# Sheet_1_2021-03-18.net
KiCad netlist of a schematic drawn in Altium Designer
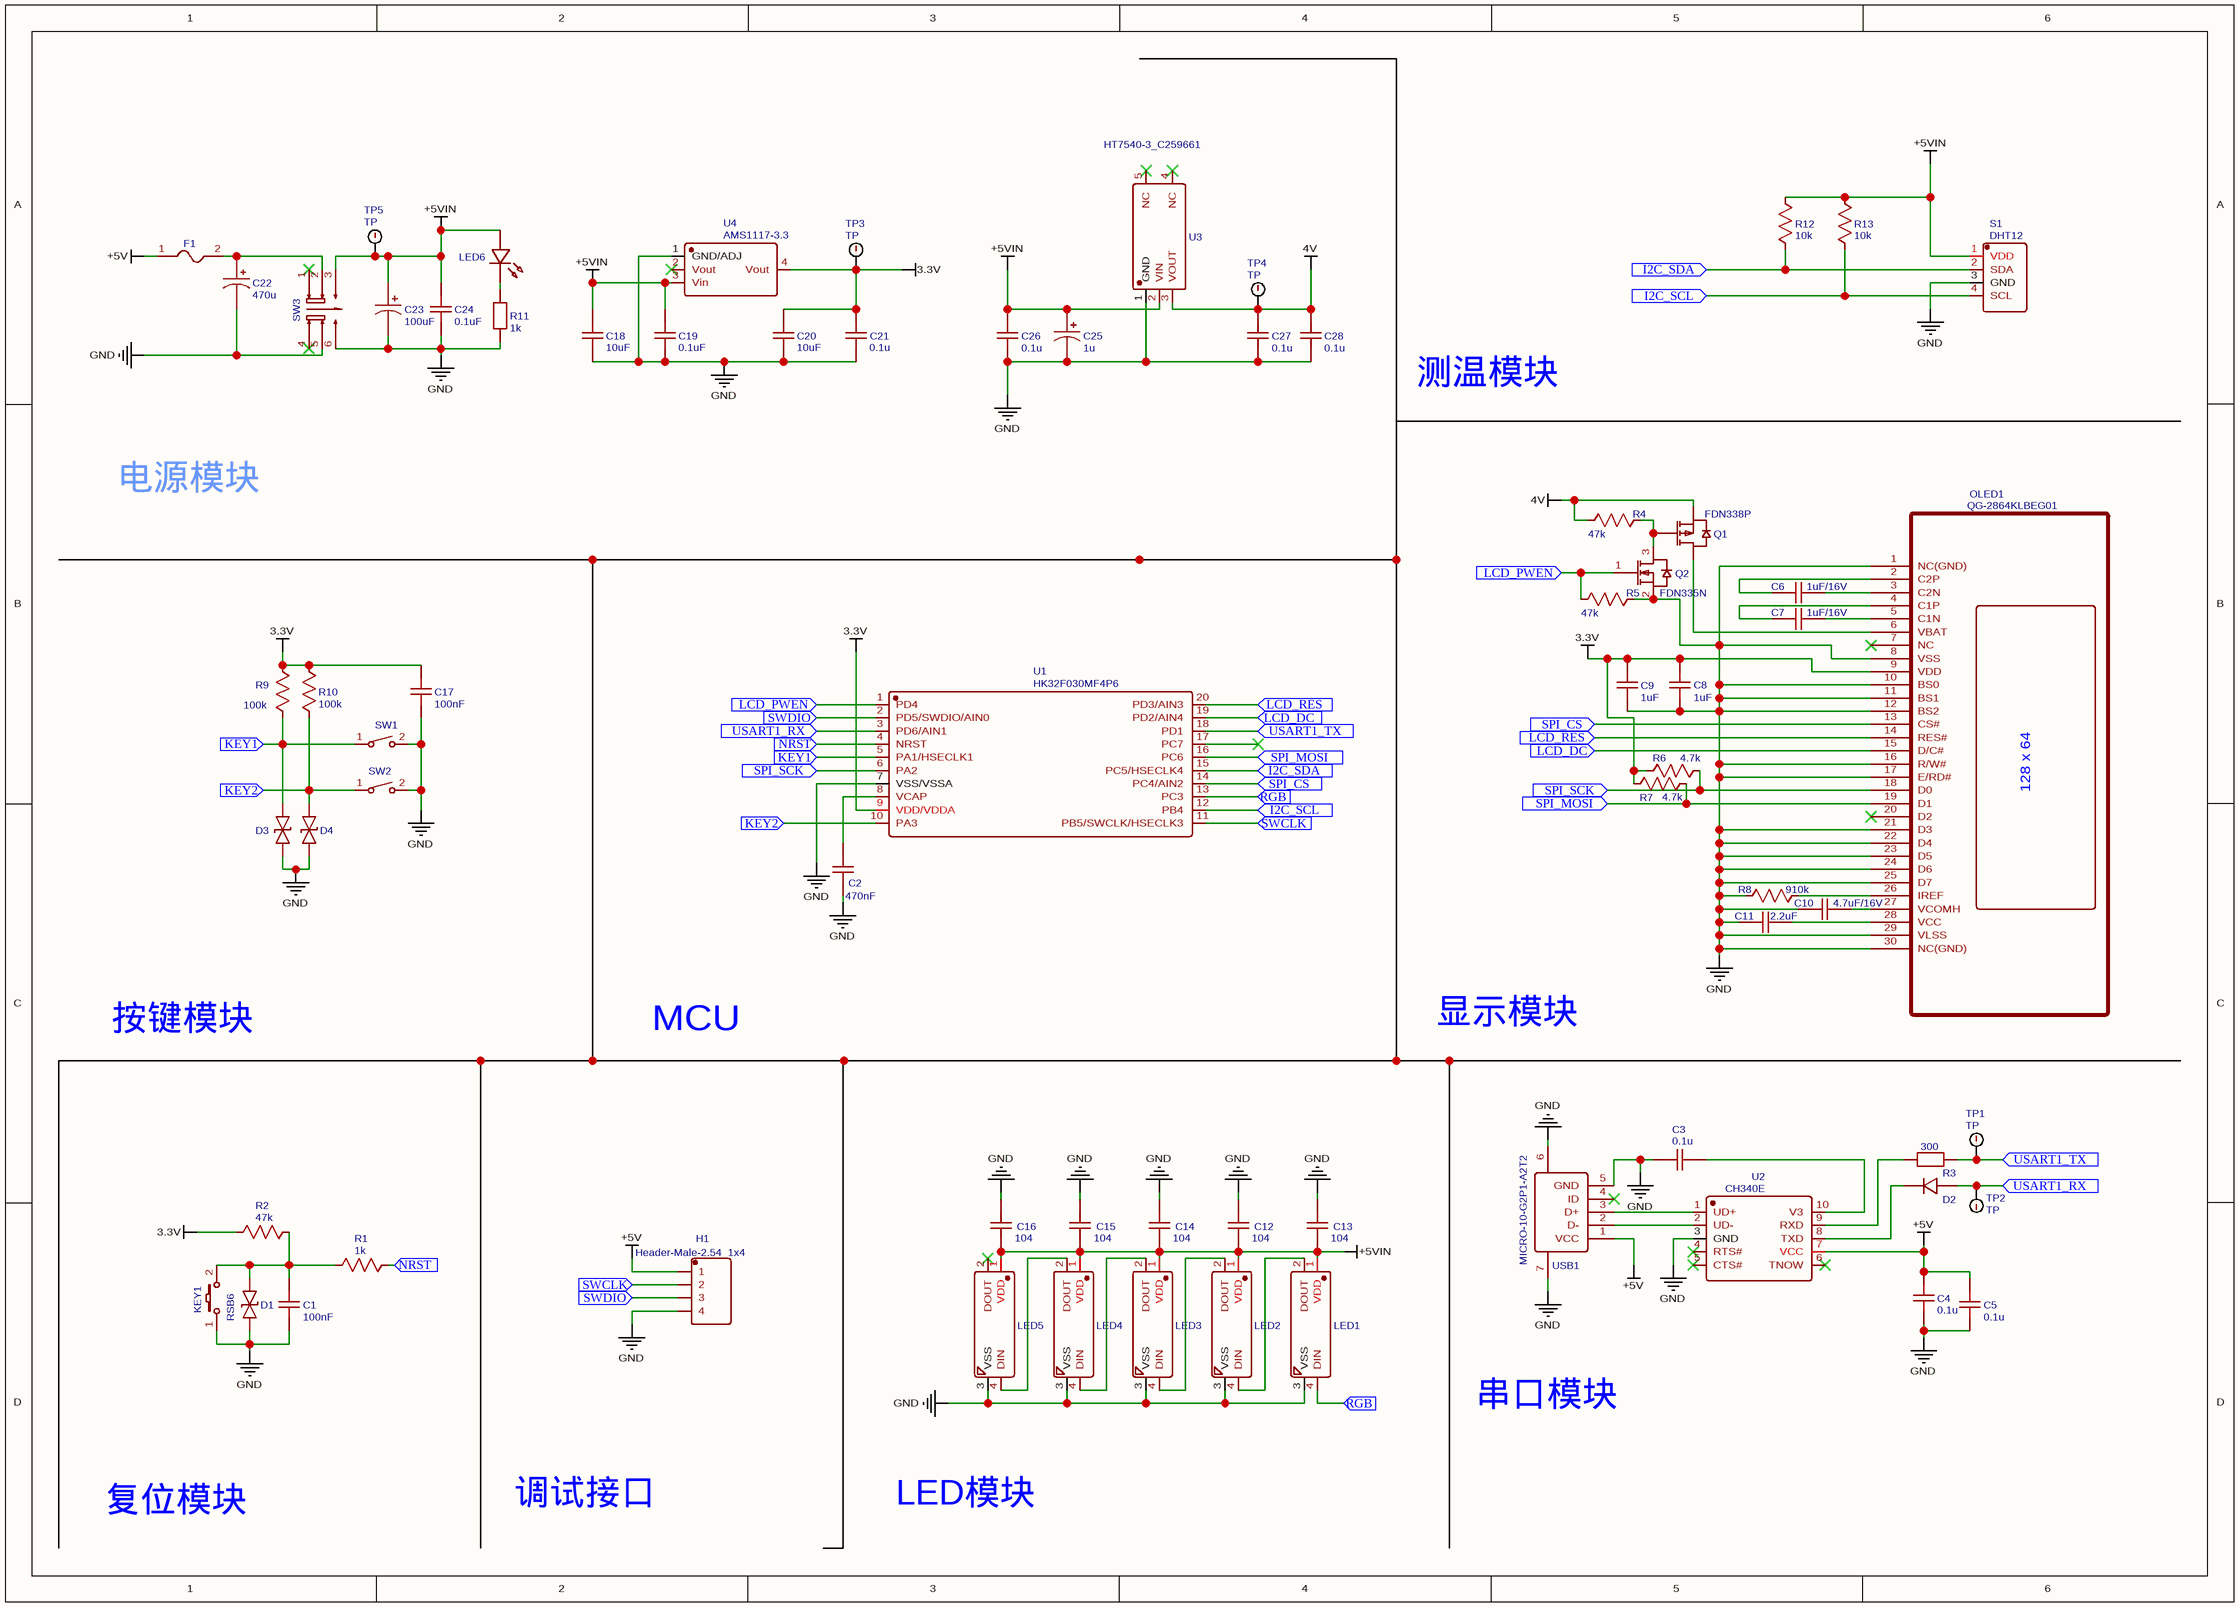
[diagram p0: Sheet_1_2021-03-18.schdoc]

(export (version "E")
  (design (tool "Eeschema 10.0.6"))
  (components
    (comp (ref "C1")
      (value "100nF")
      (fields (field (name "CONTRIBUTOR") "LCEDA_Lib"))
      (libsource (lib "altium-import") (part "root_3_100nF_"))
    )
    (comp (ref "C2")
      (value "470nF")
      (fields (field (name "CONTRIBUTOR") "LCEDA_Lib"))
      (libsource (lib "altium-import") (part "root_1_470nF_"))
    )
    (comp (ref "C3")
      (value "0.1u")
      (fields (field (name "CONTRIBUTOR") "LCEDA_Lib"))
      (libsource (lib "altium-import") (part "root_0_0.1u_"))
    )
    (comp (ref "C4")
      (value "0.1u")
      (fields (field (name "CONTRIBUTOR") "LCEDA_Lib"))
      (libsource (lib "altium-import") (part "root_1_0.1u_"))
    )
    (comp (ref "C5")
      (value "0.1u")
      (fields (field (name "CONTRIBUTOR") "LCEDA_Lib"))
      (libsource (lib "altium-import") (part "root_1_0.1u_"))
    )
    (comp (ref "C6")
      (value "1uF/16V")
      (fields (field (name "CONTRIBUTOR") "LCEDA_Lib"))
      (libsource (lib "altium-import") (part "root_0_1uF/16V_"))
    )
    (comp (ref "C7")
      (value "1uF/16V")
      (fields (field (name "CONTRIBUTOR") "LCEDA_Lib"))
      (libsource (lib "altium-import") (part "root_0_1uF/16V_"))
    )
    (comp (ref "C8")
      (value "1uF")
      (fields (field (name "CONTRIBUTOR") "LCEDA_Lib"))
      (libsource (lib "altium-import") (part "root_1_1uF_"))
    )
    (comp (ref "C9")
      (value "1uF")
      (fields (field (name "CONTRIBUTOR") "LCEDA_Lib"))
      (libsource (lib "altium-import") (part "root_1_1uF_"))
    )
    (comp (ref "C10")
      (value "4.7uF/16V")
      (fields (field (name "CONTRIBUTOR") "LCEDA_Lib"))
      (libsource (lib "altium-import") (part "root_0_4.7uF/16V_"))
    )
    (comp (ref "C11")
      (value "2.2uF")
      (fields (field (name "CONTRIBUTOR") "LCEDA_Lib"))
      (libsource (lib "altium-import") (part "root_0_2.2uF_"))
    )
    (comp (ref "C12")
      (value "104")
      (fields (field (name "CONTRIBUTOR") "LCEDA_Lib"))
      (libsource (lib "altium-import") (part "root_3_104_"))
    )
    (comp (ref "C13")
      (value "104")
      (fields (field (name "CONTRIBUTOR") "LCEDA_Lib"))
      (libsource (lib "altium-import") (part "root_3_104_"))
    )
    (comp (ref "C14")
      (value "104")
      (fields (field (name "CONTRIBUTOR") "LCEDA_Lib"))
      (libsource (lib "altium-import") (part "root_3_104_"))
    )
    (comp (ref "C15")
      (value "104")
      (fields (field (name "CONTRIBUTOR") "LCEDA_Lib"))
      (libsource (lib "altium-import") (part "root_3_104_"))
    )
    (comp (ref "C16")
      (value "104")
      (fields (field (name "CONTRIBUTOR") "LCEDA_Lib"))
      (libsource (lib "altium-import") (part "root_3_104_"))
    )
    (comp (ref "C17")
      (value "100nF")
      (fields (field (name "CONTRIBUTOR") "LCEDA_Lib"))
      (libsource (lib "altium-import") (part "root_1_100nF_"))
    )
    (comp (ref "C18")
      (value "10uF")
      (fields (field (name "CONTRIBUTOR") "LCEDA_Lib"))
      (libsource (lib "altium-import") (part "root_1_10uF_"))
    )
    (comp (ref "C19")
      (value "0.1uF")
      (fields (field (name "CONTRIBUTOR") "LCEDA_Lib"))
      (libsource (lib "altium-import") (part "root_1_0.1uF_"))
    )
    (comp (ref "C20")
      (value "10uF")
      (fields (field (name "CONTRIBUTOR") "LCEDA_Lib"))
      (libsource (lib "altium-import") (part "root_1_10uF_"))
    )
    (comp (ref "C21")
      (value "0.1u")
      (fields (field (name "CONTRIBUTOR") "LCEDA_Lib"))
      (libsource (lib "altium-import") (part "root_1_0.1u_"))
    )
    (comp (ref "C22")
      (value "470u")
      (fields (field (name "CONTRIBUTOR") "LCEDA_Lib"))
      (libsource (lib "altium-import") (part "root_3_470u_"))
    )
    (comp (ref "C23")
      (value "100uF")
      (fields (field (name "CONTRIBUTOR") "LCEDA_Lib"))
      (libsource (lib "altium-import") (part "root_3_100uF_"))
    )
    (comp (ref "C24")
      (value "0.1uF")
      (fields (field (name "CONTRIBUTOR") "LCEDA_Lib"))
      (libsource (lib "altium-import") (part "root_1_0.1uF_"))
    )
    (comp (ref "C25")
      (value "1u")
      (fields (field (name "CONTRIBUTOR") "LCEDA_Lib"))
      (libsource (lib "altium-import") (part "root_3_1u_"))
    )
    (comp (ref "C26")
      (value "0.1u")
      (fields (field (name "CONTRIBUTOR") "LCEDA_Lib"))
      (libsource (lib "altium-import") (part "root_3_0.1u_"))
    )
    (comp (ref "C27")
      (value "0.1u")
      (fields (field (name "CONTRIBUTOR") "LCEDA_Lib"))
      (libsource (lib "altium-import") (part "root_3_0.1u_"))
    )
    (comp (ref "C28")
      (value "0.1u")
      (fields (field (name "CONTRIBUTOR") "LCEDA_Lib"))
      (libsource (lib "altium-import") (part "root_3_0.1u_"))
    )
    (comp (ref "D1")
      (value "RSB6")
      (fields
        (field (name "BOM_SUPPLIER PART") "C236127")
        (field (name "BOM_MANUFACTURER PART") "RSB6.8CMGJT2N")
        (field (name "CONTRIBUTOR") "LCSC")
      )
      (libsource (lib "altium-import") (part "root_1_RSB6_"))
    )
    (comp (ref "D2")
      (value "1N4007W")
      (fields (field (name "BOM_SUPPLIER PART") "C328592") (field (name "CONTRIBUTOR") "LCEDA_Lib"))
      (libsource (lib "altium-import") (part "root_2_1N4007W_"))
    )
    (comp (ref "D3")
      (value "ESD9B5VDA-2/TR")
      (fields (field (name "BOM_SUPPLIER PART") "C506171") (field (name "CONTRIBUTOR") "LCSC"))
      (libsource (lib "altium-import") (part "root_1_ESD9B5VDA-2/TR_"))
    )
    (comp (ref "D4")
      (value "ESD9B5VDA-2/TR")
      (fields (field (name "BOM_SUPPLIER PART") "C506171") (field (name "CONTRIBUTOR") "LCSC"))
      (libsource (lib "altium-import") (part "root_1_ESD9B5VDA-2/TR_"))
    )
    (comp (ref "F1")
      (value "BSMD0805-050-6V")
      (fields (field (name "BOM_SUPPLIER PART") "C883108") (field (name "CONTRIBUTOR") "LCSC"))
      (libsource (lib "altium-import") (part "root_0_BSMD0805-050-6V_"))
    )
    (comp (ref "H1")
      (value "Header-Male-2.54_1x4")
      (fields
        (field (name "BOM_MANUFACTURER PART") "210S-1*4P L=11.6MMGold-plated black")
        (field (name "BOM_SUPPLIER PART") "C124378")
        (field (name "CONTRIBUTOR") "LCSC")
      )
      (libsource (lib "altium-import") (part "root_0_Header-Male-2.54_1x4_"))
    )
    (comp (ref "KEY1")
      (value "K2-3.6×6.1_SMD")
      (fields
        (field (name "BOM_SUPPLIER PART") "C118141")
        (field (name "BOM_MANUFACTURER PART") "K2-1107ST-A4SW-06")
        (field (name "CONTRIBUTOR") "LCEDA_Lib")
      )
      (libsource (lib "altium-import") (part "root_1_K2-3.6×6.1_SMD_"))
    )
    (comp (ref "LED1")
      (value "WS2812B")
      (fields (field (name "BOM_SUPPLIER PART") "C114585") (field (name "CONTRIBUTOR") "LCSC"))
      (libsource (lib "altium-import") (part "root_3_WS2812B_"))
    )
    (comp (ref "LED2")
      (value "WS2812B")
      (fields (field (name "BOM_SUPPLIER PART") "C114585") (field (name "CONTRIBUTOR") "LCSC"))
      (libsource (lib "altium-import") (part "root_3_WS2812B_"))
    )
    (comp (ref "LED3")
      (value "WS2812B")
      (fields (field (name "BOM_SUPPLIER PART") "C114585") (field (name "CONTRIBUTOR") "LCSC"))
      (libsource (lib "altium-import") (part "root_3_WS2812B_"))
    )
    (comp (ref "LED4")
      (value "WS2812B")
      (fields (field (name "BOM_SUPPLIER PART") "C114585") (field (name "CONTRIBUTOR") "LCSC"))
      (libsource (lib "altium-import") (part "root_3_WS2812B_"))
    )
    (comp (ref "LED5")
      (value "WS2812B")
      (fields (field (name "BOM_SUPPLIER PART") "C114585") (field (name "CONTRIBUTOR") "LCSC"))
      (libsource (lib "altium-import") (part "root_3_WS2812B_"))
    )
    (comp (ref "LED6")
      (value "LED-0603_R")
      (fields
        (field (name "BOM_MANUFACTURER PART") "19-217/R6C-AL1M2VY/3T")
        (field (name "BOM_SUPPLIER PART") "C72044")
        (field (name "CONTRIBUTOR") "LCEDA_01")
      )
      (libsource (lib "altium-import") (part "root_3_LED-0603_R_"))
    )
    (comp (ref "OLED1")
      (value "QG-2864KLBEG01")
      (fields (field (name "BOM_SUPPLIER PART") "C91755"))
      (libsource (lib "altium-import") (part "root_3_QG-2864KLBEG01_"))
    )
    (comp (ref "Q1")
      (value "FDN338P")
      (fields (field (name "BOM_SUPPLIER PART") "C24855"))
      (libsource (lib "altium-import") (part "root_2_FDN338P_"))
    )
    (comp (ref "Q2")
      (value "FDN335N")
      (fields (field (name "BOM_SUPPLIER PART") "C241804") (field (name "CONTRIBUTOR") "LCSC"))
      (libsource (lib "altium-import") (part "root_0_FDN335N_"))
    )
    (comp (ref "R1")
      (value "1k")
      (fields (field (name "CONTRIBUTOR") "LCEDA_Lib"))
      (libsource (lib "altium-import") (part "root_0_1k_"))
    )
    (comp (ref "R2")
      (value "47k")
      (fields (field (name "CONTRIBUTOR") "LCEDA_Lib"))
      (libsource (lib "altium-import") (part "root_2_47k_"))
    )
    (comp (ref "R3")
      (value "300")
      (fields (field (name "CONTRIBUTOR") "LCEDA_Lib"))
      (libsource (lib "altium-import") (part "root_0_300_"))
    )
    (comp (ref "R4")
      (value "47k")
      (fields (field (name "CONTRIBUTOR") "LCEDA_Lib"))
      (libsource (lib "altium-import") (part "root_0_47k_"))
    )
    (comp (ref "R5")
      (value "47k")
      (fields (field (name "CONTRIBUTOR") "LCEDA_Lib"))
      (libsource (lib "altium-import") (part "root_0_47k_"))
    )
    (comp (ref "R6")
      (value "4.7k")
      (fields (field (name "CONTRIBUTOR") "LCEDA_Lib"))
      (libsource (lib "altium-import") (part "root_0_4.7k_"))
    )
    (comp (ref "R7")
      (value "4.7k")
      (fields (field (name "CONTRIBUTOR") "LCEDA_Lib"))
      (libsource (lib "altium-import") (part "root_0_4.7k_"))
    )
    (comp (ref "R8")
      (value "910k")
      (fields (field (name "CONTRIBUTOR") "LCEDA_Lib"))
      (libsource (lib "altium-import") (part "root_0_910k_"))
    )
    (comp (ref "R9")
      (value "100k")
      (fields (field (name "CONTRIBUTOR") "LCEDA_Lib"))
      (libsource (lib "altium-import") (part "root_1_100k_"))
    )
    (comp (ref "R10")
      (value "100k")
      (fields (field (name "CONTRIBUTOR") "LCEDA_Lib"))
      (libsource (lib "altium-import") (part "root_1_100k_"))
    )
    (comp (ref "R11")
      (value "1k")
      (fields (field (name "CONTRIBUTOR") "LCEDA_Lib"))
      (libsource (lib "altium-import") (part "root_1_1k_"))
    )
    (comp (ref "R12")
      (value "10k")
      (fields (field (name "CONTRIBUTOR") "LCEDA_Lib"))
      (libsource (lib "altium-import") (part "root_1_10k_"))
    )
    (comp (ref "R13")
      (value "10k")
      (fields (field (name "CONTRIBUTOR") "LCEDA_Lib"))
      (libsource (lib "altium-import") (part "root_1_10k_"))
    )
    (comp (ref "S1")
      (value "DHT12")
      (fields (field (name "BOM_SUPPLIER PART") "C83989"))
      (libsource (lib "altium-import") (part "root_0_DHT12_"))
    )
    (comp (ref "SW1")
      (value "K2-1807SN-B4DW-06")
      (fields (field (name "BOM_SUPPLIER PART") "C840350") (field (name "CONTRIBUTOR") "LCSC"))
      (libsource (lib "altium-import") (part "root_0_K2-1807SN-B4DW-06_"))
    )
    (comp (ref "SW2")
      (value "K2-1807SN-B4DW-06")
      (fields (field (name "BOM_SUPPLIER PART") "C840350") (field (name "CONTRIBUTOR") "LCSC"))
      (libsource (lib "altium-import") (part "root_0_K2-1807SN-B4DW-06_"))
    )
    (comp (ref "SW3")
      (value "UK-G0701-ZS-Y")
      (fields (field (name "BOM_SUPPLIER PART") "C493256") (field (name "CONTRIBUTOR") "LCSC"))
      (libsource (lib "altium-import") (part "root_0_UK-G0701-ZS-Y_"))
    )
    (comp (ref "TP1")
      (value "TP")
      (fields (field (name "CONTRIBUTOR") "Nail3513"))
      (libsource (lib "altium-import") (part "root_0_TP_"))
    )
    (comp (ref "TP2")
      (value "TP")
      (fields (field (name "CONTRIBUTOR") "Nail3513"))
      (libsource (lib "altium-import") (part "root_2_TP_"))
    )
    (comp (ref "TP3")
      (value "TP")
      (fields (field (name "CONTRIBUTOR") "Nail3513"))
      (libsource (lib "altium-import") (part "root_0_TP_"))
    )
    (comp (ref "TP4")
      (value "TP")
      (fields (field (name "CONTRIBUTOR") "Nail3513"))
      (libsource (lib "altium-import") (part "root_0_TP_"))
    )
    (comp (ref "TP5")
      (value "TP")
      (fields (field (name "CONTRIBUTOR") "Nail3513"))
      (libsource (lib "altium-import") (part "root_0_TP_"))
    )
    (comp (ref "U1")
      (value "HK32F030MF4P6")
      (fields (field (name "BOM_SUPPLIER PART") "C707444") (field (name "CONTRIBUTOR") "LCSC"))
      (libsource (lib "altium-import") (part "root_0_HK32F030MF4P6_"))
    )
    (comp (ref "U2")
      (value "CH340E")
      (fields (field (name "BOM_SUPPLIER PART") "C99652"))
      (libsource (lib "altium-import") (part "root_2_CH340E_"))
    )
    (comp (ref "U3")
      (value "HT7540-3_C259661")
      (fields
        (field (name "BOM_SUPPLIER PART") "C259661")
        (field (name "BOM_MANUFACTURER PART") "HT7540-3")
        (field (name "CONTRIBUTOR") "LCSC")
      )
      (libsource (lib "altium-import") (part "root_1_HT7540-3_C259661_"))
    )
    (comp (ref "U4")
      (value "AMS1117-3.3")
      (fields (field (name "BOM_SUPPLIER PART") "C6186"))
      (libsource (lib "altium-import") (part "root_0_AMS1117-3.3_"))
    )
    (comp (ref "USB1")
      (value "MICRO-10-G2P1-A2T2")
      (fields (field (name "BOM_SUPPLIER PART") "C2682537") (field (name "CONTRIBUTOR") "LCSC"))
      (libsource (lib "altium-import") (part "root_2_MICRO-10-G2P1-A2T2_"))
    )
  )
  (nets
    (net (code "1") (name "+5V") (class "Default")
      (node (ref "C4") (pin "2") (pinfunction "2_2") (pintype "passive"))
      (node (ref "C5") (pin "2") (pinfunction "2_2") (pintype "passive"))
      (node (ref "F1") (pin "1") (pinfunction "1_1") (pintype "passive"))
      (node (ref "H1") (pin "1") (pinfunction "1_1") (pintype "passive"))
      (node (ref "U2") (pin "7") (pinfunction "VCC_7") (pintype "passive"))
      (node (ref "USB1") (pin "1") (pinfunction "VCC_1") (pintype "passive"))
    )
    (net (code "2") (name "+5VIN") (class "Default")
      (node (ref "C12") (pin "2") (pinfunction "2_2") (pintype "passive"))
      (node (ref "C13") (pin "2") (pinfunction "2_2") (pintype "passive"))
      (node (ref "C14") (pin "2") (pinfunction "2_2") (pintype "passive"))
      (node (ref "C15") (pin "2") (pinfunction "2_2") (pintype "passive"))
      (node (ref "C16") (pin "2") (pinfunction "2_2") (pintype "passive"))
      (node (ref "C18") (pin "2") (pinfunction "2_2") (pintype "passive"))
      (node (ref "C19") (pin "2") (pinfunction "2_2") (pintype "passive"))
      (node (ref "C23") (pin "1") (pinfunction "1_1") (pintype "passive"))
      (node (ref "C24") (pin "2") (pinfunction "2_2") (pintype "passive"))
      (node (ref "C25") (pin "1") (pinfunction "1_1") (pintype "passive"))
      (node (ref "C26") (pin "1") (pinfunction "1_1") (pintype "passive"))
      (node (ref "LED1") (pin "1") (pinfunction "VDD_1") (pintype "passive"))
      (node (ref "LED2") (pin "1") (pinfunction "VDD_1") (pintype "passive"))
      (node (ref "LED3") (pin "1") (pinfunction "VDD_1") (pintype "passive"))
      (node (ref "LED4") (pin "1") (pinfunction "VDD_1") (pintype "passive"))
      (node (ref "LED5") (pin "1") (pinfunction "VDD_1") (pintype "passive"))
      (node (ref "LED6") (pin "1") (pinfunction "1_1") (pintype "passive"))
      (node (ref "R12") (pin "2") (pinfunction "2_2") (pintype "passive"))
      (node (ref "R13") (pin "2") (pinfunction "2_2") (pintype "passive"))
      (node (ref "S1") (pin "1") (pinfunction "VDD_1") (pintype "passive"))
      (node (ref "SW3") (pin "3") (pinfunction "3_3") (pintype "passive"))
      (node (ref "TP5") (pin "1") (pinfunction "1_1") (pintype "passive"))
      (node (ref "U3") (pin "2") (pinfunction "VIN_2") (pintype "passive"))
      (node (ref "U4") (pin "3") (pinfunction "Vin_3") (pintype "passive"))
    )
    (net (code "3") (name "/I2C_SCL") (class "Default")
      (node (ref "R13") (pin "1") (pinfunction "1_1") (pintype "passive"))
      (node (ref "S1") (pin "4") (pinfunction "SCL_4") (pintype "passive"))
      (node (ref "U1") (pin "12") (pinfunction "PB4_12") (pintype "passive"))
    )
    (net (code "4") (name "/I2C_SDA") (class "Default")
      (node (ref "R12") (pin "1") (pinfunction "1_1") (pintype "passive"))
      (node (ref "S1") (pin "2") (pinfunction "SDA_2") (pintype "passive"))
      (node (ref "U1") (pin "15") (pinfunction "PC5/HSECLK4_15") (pintype "passive"))
    )
    (net (code "5") (name "/KEY1") (class "Default")
      (node (ref "D3") (pin "2") (pinfunction "2_2") (pintype "passive"))
      (node (ref "R9") (pin "1") (pinfunction "1_1") (pintype "passive"))
      (node (ref "SW1") (pin "1") (pinfunction "1_1") (pintype "passive"))
      (node (ref "U1") (pin "5") (pinfunction "PA1/HSECLK1_5") (pintype "passive"))
    )
    (net (code "6") (name "/KEY2") (class "Default")
      (node (ref "D4") (pin "2") (pinfunction "2_2") (pintype "passive"))
      (node (ref "R10") (pin "1") (pinfunction "1_1") (pintype "passive"))
      (node (ref "SW2") (pin "1") (pinfunction "1_1") (pintype "passive"))
      (node (ref "U1") (pin "10") (pinfunction "PA3_10") (pintype "passive"))
    )
    (net (code "7") (name "/LCD_DC") (class "Default")
      (node (ref "OLED1") (pin "15") (pinfunction "D/C#_15") (pintype "passive"))
      (node (ref "U1") (pin "19") (pinfunction "PD2/AIN4_19") (pintype "passive"))
    )
    (net (code "8") (name "/LCD_PWEN") (class "Default")
      (node (ref "Q2") (pin "1") (pinfunction "G_1") (pintype "passive"))
      (node (ref "R5") (pin "1") (pinfunction "1_1") (pintype "passive"))
      (node (ref "U1") (pin "1") (pinfunction "PD4_1") (pintype "passive"))
    )
    (net (code "9") (name "/LCD_RES") (class "Default")
      (node (ref "OLED1") (pin "14") (pinfunction "RES#_14") (pintype "passive"))
      (node (ref "U1") (pin "20") (pinfunction "PD3/AIN3_20") (pintype "passive"))
    )
    (net (code "10") (name "/NRST") (class "Default")
      (node (ref "R1") (pin "2") (pinfunction "2_2") (pintype "passive"))
      (node (ref "U1") (pin "4") (pinfunction "NRST_4") (pintype "passive"))
    )
    (net (code "11") (name "/RGB") (class "Default")
      (node (ref "LED1") (pin "4") (pinfunction "DIN_4") (pintype "passive"))
      (node (ref "U1") (pin "13") (pinfunction "PC3_13") (pintype "passive"))
    )
    (net (code "12") (name "/SPI_CS") (class "Default")
      (node (ref "OLED1") (pin "13") (pinfunction "CS#_13") (pintype "passive"))
      (node (ref "U1") (pin "14") (pinfunction "PC4/AIN2_14") (pintype "passive"))
    )
    (net (code "13") (name "/SPI_MOSI") (class "Default")
      (node (ref "OLED1") (pin "19") (pinfunction "D1_19") (pintype "passive"))
      (node (ref "R7") (pin "2") (pinfunction "2_2") (pintype "passive"))
      (node (ref "U1") (pin "16") (pinfunction "PC6_16") (pintype "passive"))
    )
    (net (code "14") (name "/SPI_SCK") (class "Default")
      (node (ref "OLED1") (pin "18") (pinfunction "D0_18") (pintype "passive"))
      (node (ref "R6") (pin "2") (pinfunction "2_2") (pintype "passive"))
      (node (ref "U1") (pin "6") (pinfunction "PA2_6") (pintype "passive"))
    )
    (net (code "15") (name "/SWCLK") (class "Default")
      (node (ref "H1") (pin "2") (pinfunction "2_2") (pintype "passive"))
      (node (ref "U1") (pin "11") (pinfunction "PB5/SWCLK/HSECLK3_11") (pintype "passive"))
    )
    (net (code "16") (name "/SWDIO") (class "Default")
      (node (ref "H1") (pin "3") (pinfunction "3_3") (pintype "passive"))
      (node (ref "U1") (pin "2") (pinfunction "PD5/SWDIO/AIN0_2") (pintype "passive"))
    )
    (net (code "17") (name "/USART1_RX") (class "Default")
      (node (ref "D2") (pin "2") (pinfunction "2_2") (pintype "passive"))
      (node (ref "TP2") (pin "1") (pinfunction "1_1") (pintype "passive"))
      (node (ref "U1") (pin "3") (pinfunction "PD6/AIN1_3") (pintype "passive"))
    )
    (net (code "18") (name "/USART1_TX") (class "Default")
      (node (ref "R3") (pin "2") (pinfunction "2_2") (pintype "passive"))
      (node (ref "TP1") (pin "1") (pinfunction "1_1") (pintype "passive"))
      (node (ref "U1") (pin "18") (pinfunction "PD1_18") (pintype "passive"))
    )
    (net (code "19") (name "3.3V") (class "Default")
      (node (ref "C17") (pin "2") (pinfunction "2_2") (pintype "passive"))
      (node (ref "C20") (pin "2") (pinfunction "2_2") (pintype "passive"))
      (node (ref "C21") (pin "2") (pinfunction "2_2") (pintype "passive"))
      (node (ref "C8") (pin "2") (pinfunction "2_2") (pintype "passive"))
      (node (ref "C9") (pin "2") (pinfunction "2_2") (pintype "passive"))
      (node (ref "OLED1") (pin "9") (pinfunction "VDD_9") (pintype "passive"))
      (node (ref "R10") (pin "2") (pinfunction "2_2") (pintype "passive"))
      (node (ref "R2") (pin "2") (pinfunction "2_2") (pintype "passive"))
      (node (ref "R6") (pin "1") (pinfunction "1_1") (pintype "passive"))
      (node (ref "R7") (pin "1") (pinfunction "1_1") (pintype "passive"))
      (node (ref "R9") (pin "2") (pinfunction "2_2") (pintype "passive"))
      (node (ref "TP3") (pin "1") (pinfunction "1_1") (pintype "passive"))
      (node (ref "U1") (pin "9") (pinfunction "VDD/VDDA_9") (pintype "passive"))
      (node (ref "U4") (pin "4") (pinfunction "Vout_4") (pintype "passive"))
    )
    (net (code "20") (name "4V") (class "Default")
      (node (ref "C27") (pin "1") (pinfunction "1_1") (pintype "passive"))
      (node (ref "C28") (pin "1") (pinfunction "1_1") (pintype "passive"))
      (node (ref "Q1") (pin "2") (pinfunction "S_2") (pintype "passive"))
      (node (ref "R4") (pin "1") (pinfunction "1_1") (pintype "passive"))
      (node (ref "TP4") (pin "1") (pinfunction "1_1") (pintype "passive"))
      (node (ref "U3") (pin "3") (pinfunction "VOUT_3") (pintype "passive"))
    )
    (net (code "21") (name "GND") (class "Default")
      (node (ref "C1") (pin "2") (pinfunction "2_2") (pintype "passive"))
      (node (ref "C10") (pin "1") (pinfunction "1_1") (pintype "passive"))
      (node (ref "C11") (pin "1") (pinfunction "1_1") (pintype "passive"))
      (node (ref "C12") (pin "1") (pinfunction "1_1") (pintype "passive"))
      (node (ref "C13") (pin "1") (pinfunction "1_1") (pintype "passive"))
      (node (ref "C14") (pin "1") (pinfunction "1_1") (pintype "passive"))
      (node (ref "C15") (pin "1") (pinfunction "1_1") (pintype "passive"))
      (node (ref "C16") (pin "1") (pinfunction "1_1") (pintype "passive"))
      (node (ref "C17") (pin "1") (pinfunction "1_1") (pintype "passive"))
      (node (ref "C18") (pin "1") (pinfunction "1_1") (pintype "passive"))
      (node (ref "C19") (pin "1") (pinfunction "1_1") (pintype "passive"))
      (node (ref "C2") (pin "1") (pinfunction "1_1") (pintype "passive"))
      (node (ref "C20") (pin "1") (pinfunction "1_1") (pintype "passive"))
      (node (ref "C21") (pin "1") (pinfunction "1_1") (pintype "passive"))
      (node (ref "C22") (pin "2") (pinfunction "2_2") (pintype "passive"))
      (node (ref "C23") (pin "2") (pinfunction "2_2") (pintype "passive"))
      (node (ref "C24") (pin "1") (pinfunction "1_1") (pintype "passive"))
      (node (ref "C25") (pin "2") (pinfunction "2_2") (pintype "passive"))
      (node (ref "C26") (pin "2") (pinfunction "2_2") (pintype "passive"))
      (node (ref "C27") (pin "2") (pinfunction "2_2") (pintype "passive"))
      (node (ref "C28") (pin "2") (pinfunction "2_2") (pintype "passive"))
      (node (ref "C3") (pin "1") (pinfunction "1_1") (pintype "passive"))
      (node (ref "C4") (pin "1") (pinfunction "1_1") (pintype "passive"))
      (node (ref "C5") (pin "1") (pinfunction "1_1") (pintype "passive"))
      (node (ref "C8") (pin "1") (pinfunction "1_1") (pintype "passive"))
      (node (ref "C9") (pin "1") (pinfunction "1_1") (pintype "passive"))
      (node (ref "D1") (pin "1") (pinfunction "1_1") (pintype "passive"))
      (node (ref "D3") (pin "1") (pinfunction "1_1") (pintype "passive"))
      (node (ref "D4") (pin "1") (pinfunction "1_1") (pintype "passive"))
      (node (ref "H1") (pin "4") (pinfunction "4_4") (pintype "passive"))
      (node (ref "KEY1") (pin "1") (pinfunction "1_1") (pintype "passive"))
      (node (ref "LED1") (pin "3") (pinfunction "VSS_3") (pintype "passive"))
      (node (ref "LED2") (pin "3") (pinfunction "VSS_3") (pintype "passive"))
      (node (ref "LED3") (pin "3") (pinfunction "VSS_3") (pintype "passive"))
      (node (ref "LED4") (pin "3") (pinfunction "VSS_3") (pintype "passive"))
      (node (ref "LED5") (pin "3") (pinfunction "VSS_3") (pintype "passive"))
      (node (ref "OLED1") (pin "1") (pinfunction "NC(GND)_1") (pintype "passive"))
      (node (ref "OLED1") (pin "10") (pinfunction "BS0_10") (pintype "passive"))
      (node (ref "OLED1") (pin "11") (pinfunction "BS1_11") (pintype "passive"))
      (node (ref "OLED1") (pin "12") (pinfunction "BS2_12") (pintype "passive"))
      (node (ref "OLED1") (pin "16") (pinfunction "R/W#_16") (pintype "passive"))
      (node (ref "OLED1") (pin "17") (pinfunction "E/RD#_17") (pintype "passive"))
      (node (ref "OLED1") (pin "21") (pinfunction "D3_21") (pintype "passive"))
      (node (ref "OLED1") (pin "22") (pinfunction "D4_22") (pintype "passive"))
      (node (ref "OLED1") (pin "23") (pinfunction "D5_23") (pintype "passive"))
      (node (ref "OLED1") (pin "24") (pinfunction "D6_24") (pintype "passive"))
      (node (ref "OLED1") (pin "25") (pinfunction "D7_25") (pintype "passive"))
      (node (ref "OLED1") (pin "29") (pinfunction "VLSS_29") (pintype "passive"))
      (node (ref "OLED1") (pin "30") (pinfunction "NC(GND)_30") (pintype "passive"))
      (node (ref "OLED1") (pin "8") (pinfunction "VSS_8") (pintype "passive"))
      (node (ref "Q2") (pin "2") (pinfunction "S_2") (pintype "passive"))
      (node (ref "R11") (pin "1") (pinfunction "1_1") (pintype "passive"))
      (node (ref "R5") (pin "2") (pinfunction "2_2") (pintype "passive"))
      (node (ref "R8") (pin "1") (pinfunction "1_1") (pintype "passive"))
      (node (ref "S1") (pin "3") (pinfunction "GND_3") (pintype "passive"))
      (node (ref "SW1") (pin "2") (pinfunction "2_2") (pintype "passive"))
      (node (ref "SW2") (pin "2") (pinfunction "2_2") (pintype "passive"))
      (node (ref "SW3") (pin "5") (pinfunction "5_5") (pintype "passive"))
      (node (ref "SW3") (pin "6") (pinfunction "6_6") (pintype "passive"))
      (node (ref "U1") (pin "7") (pinfunction "VSS/VSSA_7") (pintype "passive"))
      (node (ref "U2") (pin "3") (pinfunction "GND_3") (pintype "passive"))
      (node (ref "U3") (pin "1") (pinfunction "GND_1") (pintype "passive"))
      (node (ref "U4") (pin "1") (pinfunction "GND/ADJ_1") (pintype "passive"))
      (node (ref "USB1") (pin "5") (pinfunction "GND_5") (pintype "passive"))
      (node (ref "USB1") (pin "6") (pinfunction "6_6") (pintype "passive"))
      (node (ref "USB1") (pin "7") (pinfunction "7_7") (pintype "passive"))
    )
    (net (code "22") (name "Net-(C1-Pad1)") (class "Default")
      (node (ref "C1") (pin "1") (pinfunction "1_1") (pintype "passive"))
      (node (ref "D1") (pin "2") (pinfunction "2_2") (pintype "passive"))
      (node (ref "KEY1") (pin "2") (pinfunction "2_2") (pintype "passive"))
      (node (ref "R1") (pin "1") (pinfunction "1_1") (pintype "passive"))
      (node (ref "R2") (pin "1") (pinfunction "1_1") (pintype "passive"))
    )
    (net (code "23") (name "Net-(C22-Pad1)") (class "Default")
      (node (ref "C22") (pin "1") (pinfunction "1_1") (pintype "passive"))
      (node (ref "F1") (pin "2") (pinfunction "2_2") (pintype "passive"))
      (node (ref "SW3") (pin "2") (pinfunction "2_2") (pintype "passive"))
    )
    (net (code "24") (name "Net-(LED1-DOUT)") (class "Default")
      (node (ref "LED1") (pin "2") (pinfunction "DOUT_2") (pintype "passive"))
      (node (ref "LED2") (pin "4") (pinfunction "DIN_4") (pintype "passive"))
    )
    (net (code "25") (name "Net-(LED2-DOUT)") (class "Default")
      (node (ref "LED2") (pin "2") (pinfunction "DOUT_2") (pintype "passive"))
      (node (ref "LED3") (pin "4") (pinfunction "DIN_4") (pintype "passive"))
    )
    (net (code "26") (name "Net-(LED3-DOUT)") (class "Default")
      (node (ref "LED3") (pin "2") (pinfunction "DOUT_2") (pintype "passive"))
      (node (ref "LED4") (pin "4") (pinfunction "DIN_4") (pintype "passive"))
    )
    (net (code "27") (name "Net-(LED4-DOUT)") (class "Default")
      (node (ref "LED4") (pin "2") (pinfunction "DOUT_2") (pintype "passive"))
      (node (ref "LED5") (pin "4") (pinfunction "DIN_4") (pintype "passive"))
    )
    (net (code "28") (name "Net-(LED6-Pad2)") (class "Default")
      (node (ref "LED6") (pin "2") (pinfunction "2_2") (pintype "passive"))
      (node (ref "R11") (pin "2") (pinfunction "2_2") (pintype "passive"))
    )
    (net (code "29") (name "Net-(OLED1-C1N)") (class "Default")
      (node (ref "C7") (pin "2") (pinfunction "2_2") (pintype "passive"))
      (node (ref "OLED1") (pin "5") (pinfunction "C1N_5") (pintype "passive"))
    )
    (net (code "30") (name "Net-(OLED1-C1P)") (class "Default")
      (node (ref "C7") (pin "1") (pinfunction "1_1") (pintype "passive"))
      (node (ref "OLED1") (pin "4") (pinfunction "C1P_4") (pintype "passive"))
    )
    (net (code "31") (name "Net-(OLED1-C2N)") (class "Default")
      (node (ref "C6") (pin "2") (pinfunction "2_2") (pintype "passive"))
      (node (ref "OLED1") (pin "3") (pinfunction "C2N_3") (pintype "passive"))
    )
    (net (code "32") (name "Net-(OLED1-C2P)") (class "Default")
      (node (ref "C6") (pin "1") (pinfunction "1_1") (pintype "passive"))
      (node (ref "OLED1") (pin "2") (pinfunction "C2P_2") (pintype "passive"))
    )
    (net (code "33") (name "Net-(OLED1-IREF)") (class "Default")
      (node (ref "OLED1") (pin "26") (pinfunction "IREF_26") (pintype "passive"))
      (node (ref "R8") (pin "2") (pinfunction "2_2") (pintype "passive"))
    )
    (net (code "34") (name "Net-(OLED1-VBAT)") (class "Default")
      (node (ref "OLED1") (pin "6") (pinfunction "VBAT_6") (pintype "passive"))
      (node (ref "Q1") (pin "3") (pinfunction "D_3") (pintype "passive"))
    )
    (net (code "35") (name "Net-(OLED1-VCC)") (class "Default")
      (node (ref "C11") (pin "2") (pinfunction "2_2") (pintype "passive"))
      (node (ref "OLED1") (pin "28") (pinfunction "VCC_28") (pintype "passive"))
    )
    (net (code "36") (name "Net-(OLED1-VCOMH)") (class "Default")
      (node (ref "C10") (pin "2") (pinfunction "2_2") (pintype "passive"))
      (node (ref "OLED1") (pin "27") (pinfunction "VCOMH_27") (pintype "passive"))
    )
    (net (code "37") (name "Net-(Q1-G)") (class "Default")
      (node (ref "Q1") (pin "1") (pinfunction "G_1") (pintype "passive"))
      (node (ref "Q2") (pin "3") (pinfunction "D_3") (pintype "passive"))
      (node (ref "R4") (pin "2") (pinfunction "2_2") (pintype "passive"))
    )
    (net (code "38") (name "Net-(U1-VCAP)") (class "Default")
      (node (ref "C2") (pin "2") (pinfunction "2_2") (pintype "passive"))
      (node (ref "U1") (pin "8") (pinfunction "VCAP_8") (pintype "passive"))
    )
    (net (code "39") (name "Net-(U2-RXD)") (class "Default")
      (node (ref "R3") (pin "1") (pinfunction "1_1") (pintype "passive"))
      (node (ref "U2") (pin "9") (pinfunction "RXD_9") (pintype "passive"))
    )
    (net (code "40") (name "Net-(U2-TXD)") (class "Default")
      (node (ref "D2") (pin "1") (pinfunction "1_1") (pintype "passive"))
      (node (ref "U2") (pin "8") (pinfunction "TXD_8") (pintype "passive"))
    )
    (net (code "41") (name "Net-(U2-UD+)") (class "Default")
      (node (ref "U2") (pin "1") (pinfunction "UD+_1") (pintype "passive"))
      (node (ref "USB1") (pin "3") (pinfunction "D+_3") (pintype "passive"))
    )
    (net (code "42") (name "Net-(U2-UD-)") (class "Default")
      (node (ref "U2") (pin "2") (pinfunction "UD-_2") (pintype "passive"))
      (node (ref "USB1") (pin "2") (pinfunction "D-_2") (pintype "passive"))
    )
    (net (code "43") (name "Net-(U2-V3)") (class "Default")
      (node (ref "C3") (pin "2") (pinfunction "2_2") (pintype "passive"))
      (node (ref "U2") (pin "10") (pinfunction "V3_10") (pintype "passive"))
    )
    (net (code "44") (name "unconnected-(LED5-DOUT-Pad2)") (class "Default")
      (node (ref "LED5") (pin "2") (pinfunction "DOUT_2") (pintype "passive+no_connect"))
    )
    (net (code "45") (name "unconnected-(OLED1-D2-Pad20)") (class "Default")
      (node (ref "OLED1") (pin "20") (pinfunction "D2_20") (pintype "passive+no_connect"))
    )
    (net (code "46") (name "unconnected-(OLED1-NC-Pad7)") (class "Default")
      (node (ref "OLED1") (pin "7") (pinfunction "NC_7") (pintype "passive+no_connect"))
    )
    (net (code "47") (name "unconnected-(SW3-Pad1)") (class "Default")
      (node (ref "SW3") (pin "1") (pinfunction "1_1") (pintype "passive+no_connect"))
    )
    (net (code "48") (name "unconnected-(SW3-Pad4)") (class "Default")
      (node (ref "SW3") (pin "4") (pinfunction "4_4") (pintype "passive+no_connect"))
    )
    (net (code "49") (name "unconnected-(U1-PC7-Pad17)") (class "Default")
      (node (ref "U1") (pin "17") (pinfunction "PC7_17") (pintype "passive+no_connect"))
    )
    (net (code "50") (name "unconnected-(U2-CTS#-Pad5)") (class "Default")
      (node (ref "U2") (pin "5") (pinfunction "CTS#_5") (pintype "passive+no_connect"))
    )
    (net (code "51") (name "unconnected-(U2-RTS#-Pad4)") (class "Default")
      (node (ref "U2") (pin "4") (pinfunction "RTS#_4") (pintype "passive+no_connect"))
    )
    (net (code "52") (name "unconnected-(U2-TNOW-Pad6)") (class "Default")
      (node (ref "U2") (pin "6") (pinfunction "TNOW_6") (pintype "passive+no_connect"))
    )
    (net (code "53") (name "unconnected-(U3-NC-Pad4)") (class "Default")
      (node (ref "U3") (pin "4") (pinfunction "NC_4") (pintype "passive+no_connect"))
    )
    (net (code "54") (name "unconnected-(U3-NC-Pad5)") (class "Default")
      (node (ref "U3") (pin "5") (pinfunction "NC_5") (pintype "passive+no_connect"))
    )
    (net (code "55") (name "unconnected-(U4-Vout-Pad2)") (class "Default")
      (node (ref "U4") (pin "2") (pinfunction "Vout_2") (pintype "passive+no_connect"))
    )
    (net (code "56") (name "unconnected-(USB1-ID-Pad4)") (class "Default")
      (node (ref "USB1") (pin "4") (pinfunction "ID_4") (pintype "passive+no_connect"))
    )
  )
)
